# kegmon_hx711.net
KiCad netlist of a schematic drawn in EAGLE
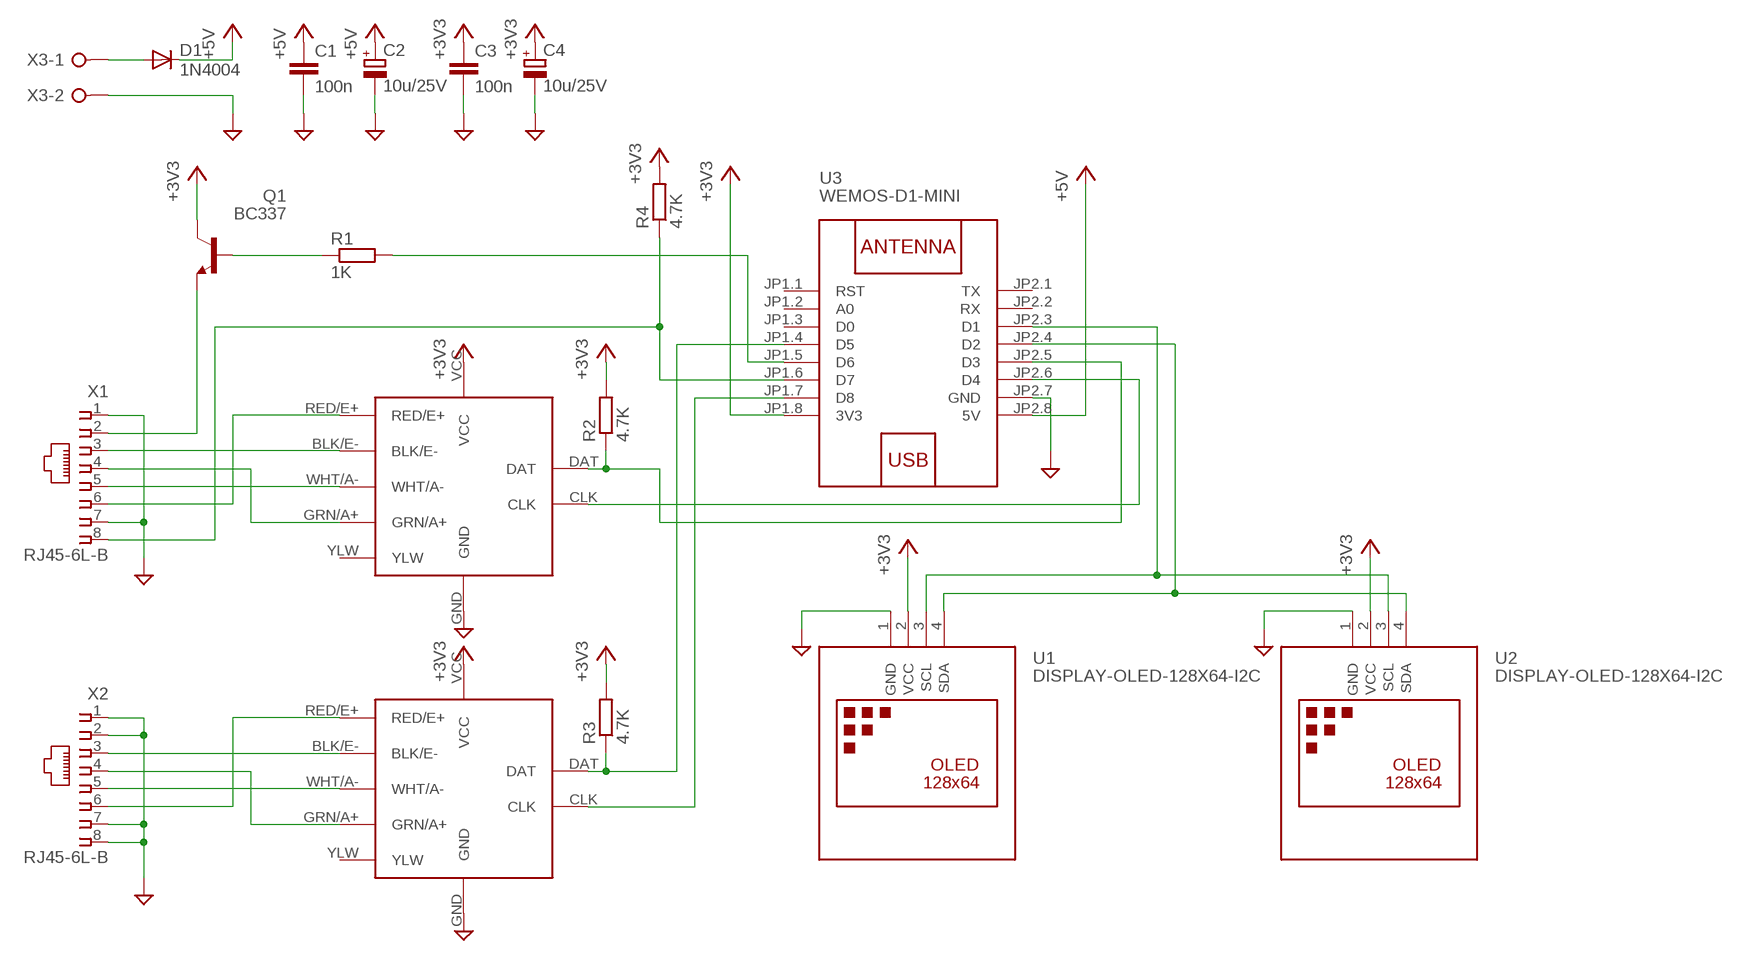
[diagram p0: schematic, sheet 1]

(export (version "E")
  (design (tool "Eeschema 10.0.6"))
  (components
    (comp (ref "C1")
      (value "100n")
      (footprint "eagle-import:C050-025X075")
      (libsource (lib "eagle-import") (part "C-EU050-025X075"))
    )
    (comp (ref "C2")
      (value "10u/25V")
      (footprint "eagle-import:E2,5-5")
      (libsource (lib "eagle-import") (part "CPOL-EUE2.5-5"))
    )
    (comp (ref "C3")
      (value "100n")
      (footprint "eagle-import:C050-025X075")
      (libsource (lib "eagle-import") (part "C-EU050-025X075"))
    )
    (comp (ref "C4")
      (value "10u/25V")
      (footprint "eagle-import:E2,5-5")
      (libsource (lib "eagle-import") (part "CPOL-EUE2.5-5"))
    )
    (comp (ref "D1")
      (value "1N4004")
      (footprint "eagle-import:DO41-10")
      (libsource (lib "eagle-import") (part "1N4004"))
    )
    (comp (ref "IC1")
      (value "SPARKFUN-HX711")
      (footprint "eagle-import:SPARKFUN-HX711")
      (libsource (lib "eagle-import") (part "SPARKFUN-HX711"))
    )
    (comp (ref "IC2")
      (value "SPARKFUN-HX711")
      (footprint "eagle-import:SPARKFUN-HX711")
      (libsource (lib "eagle-import") (part "SPARKFUN-HX711"))
    )
    (comp (ref "Q1")
      (value "BC337")
      (footprint "eagle-import:TO92")
      (libsource (lib "eagle-import") (part "BC337"))
    )
    (comp (ref "R1")
      (value "1K")
      (footprint "eagle-import:0207_10")
      (libsource (lib "eagle-import") (part "R-EU_0207/10"))
    )
    (comp (ref "R2")
      (value "4.7K")
      (footprint "eagle-import:0207_10")
      (libsource (lib "eagle-import") (part "R-EU_0207/10"))
    )
    (comp (ref "R3")
      (value "4.7K")
      (footprint "eagle-import:0207_10")
      (libsource (lib "eagle-import") (part "R-EU_0207/10"))
    )
    (comp (ref "R4")
      (value "4.7K")
      (footprint "eagle-import:0207_10")
      (libsource (lib "eagle-import") (part "R-EU_0207/10"))
    )
    (comp (ref "U1")
      (value "DISPLAY-OLED-128X64-I2C")
      (footprint "eagle-import:DISPLAY-OLED-128X64-I2C-NOHOLES")
      (libsource (lib "eagle-import") (part "DISPLAY-OLED-128X64-I2CDISPLAY-OLED-128X64-I2C-NOHOLES"))
    )
    (comp (ref "U2")
      (value "DISPLAY-OLED-128X64-I2C")
      (footprint "eagle-import:DISPLAY-OLED-128X64-I2C-NOHOLES")
      (libsource (lib "eagle-import") (part "DISPLAY-OLED-128X64-I2CDISPLAY-OLED-128X64-I2C-NOHOLES"))
    )
    (comp (ref "U3")
      (value "WEMOS-D1-MINI")
      (footprint "eagle-import:WEMOS-D1-MINI")
      (libsource (lib "eagle-import") (part "WEMOS-D1-MINI"))
    )
    (comp (ref "X1")
      (value "RJ45-6L-B")
      (footprint "eagle-import:RJ45-NO-SHIELD")
      (libsource (lib "eagle-import") (part "RJ45-6L-B"))
    )
    (comp (ref "X2")
      (value "RJ45-6L-B")
      (footprint "eagle-import:RJ45-NO-SHIELD")
      (libsource (lib "eagle-import") (part "RJ45-6L-B"))
    )
    (comp (ref "X3")
      (value "W237-02P")
      (footprint "eagle-import:W237-132")
      (libsource (lib "eagle-import") (part "W237-02P"))
    )
  )
  (nets
    (net (code "1") (name "+3V3") (class "Default")
      (node (ref "C3") (pin "1") (pinfunction "1_1") (pintype "passive"))
      (node (ref "C4") (pin "+") (pinfunction "+_+") (pintype "passive"))
      (node (ref "IC1") (pin "VCC") (pinfunction "VCC_VCC") (pintype "bidirectional"))
      (node (ref "IC2") (pin "VCC") (pinfunction "VCC_VCC") (pintype "bidirectional"))
      (node (ref "Q1") (pin "3") (pinfunction "C_3") (pintype "passive"))
      (node (ref "R2") (pin "2") (pinfunction "2_2") (pintype "passive"))
      (node (ref "R3") (pin "2") (pinfunction "2_2") (pintype "passive"))
      (node (ref "R4") (pin "2") (pinfunction "2_2") (pintype "passive"))
      (node (ref "U1") (pin "2") (pinfunction "VCC_2") (pintype "power_in"))
      (node (ref "U2") (pin "2") (pinfunction "VCC_2") (pintype "power_in"))
      (node (ref "U3") (pin "JP1.8") (pinfunction "3V3_JP1.8") (pintype "power_in"))
    )
    (net (code "2") (name "+5V") (class "Default")
      (node (ref "C1") (pin "1") (pinfunction "1_1") (pintype "passive"))
      (node (ref "C2") (pin "+") (pinfunction "+_+") (pintype "passive"))
      (node (ref "D1") (pin "C") (pinfunction "C_C") (pintype "passive"))
      (node (ref "U3") (pin "JP2.8") (pinfunction "5V_JP2.8") (pintype "power_in"))
    )
    (net (code "3") (name "GND") (class "Default")
      (node (ref "C1") (pin "2") (pinfunction "2_2") (pintype "passive"))
      (node (ref "C2") (pin "-") (pinfunction "-_-") (pintype "passive"))
      (node (ref "C3") (pin "2") (pinfunction "2_2") (pintype "passive"))
      (node (ref "C4") (pin "-") (pinfunction "-_-") (pintype "passive"))
      (node (ref "IC1") (pin "GND") (pinfunction "GND_GND") (pintype "bidirectional"))
      (node (ref "IC2") (pin "GND") (pinfunction "GND_GND") (pintype "bidirectional"))
      (node (ref "U1") (pin "1") (pinfunction "GND_1") (pintype "power_in"))
      (node (ref "U2") (pin "1") (pinfunction "GND_1") (pintype "power_in"))
      (node (ref "U3") (pin "JP2.7") (pinfunction "GND_JP2.7") (pintype "power_in"))
      (node (ref "X1") (pin "1") (pinfunction "1_1") (pintype "passive"))
      (node (ref "X1") (pin "7") (pinfunction "7_7") (pintype "passive"))
      (node (ref "X2") (pin "1") (pinfunction "1_1") (pintype "passive"))
      (node (ref "X2") (pin "2") (pinfunction "2_2") (pintype "passive"))
      (node (ref "X2") (pin "7") (pinfunction "7_7") (pintype "passive"))
      (node (ref "X2") (pin "8") (pinfunction "8_8") (pintype "passive"))
      (node (ref "X3") (pin "2") (pinfunction "KL_2") (pintype "passive"))
    )
    (net (code "4") (name "Net-(IC1-PadBLK{slash}E-)") (class "Default")
      (node (ref "IC1") (pin "BLK/E-") (pinfunction "BLK/E-_BLK/E-") (pintype "bidirectional"))
      (node (ref "X1") (pin "3") (pinfunction "3_3") (pintype "passive"))
    )
    (net (code "5") (name "Net-(IC1-PadGRN{slash}A+)") (class "Default")
      (node (ref "IC1") (pin "GRN/A+") (pinfunction "GRN/A+_GRN/A+") (pintype "bidirectional"))
      (node (ref "X1") (pin "4") (pinfunction "4_4") (pintype "passive"))
    )
    (net (code "6") (name "Net-(IC1-PadRED{slash}E+)") (class "Default")
      (node (ref "IC1") (pin "RED/E+") (pinfunction "RED/E+_RED/E+") (pintype "bidirectional"))
      (node (ref "X1") (pin "6") (pinfunction "6_6") (pintype "passive"))
    )
    (net (code "7") (name "Net-(IC1-PadWHT{slash}A-)") (class "Default")
      (node (ref "IC1") (pin "WHT/A-") (pinfunction "WHT/A-_WHT/A-") (pintype "bidirectional"))
      (node (ref "X1") (pin "5") (pinfunction "5_5") (pintype "passive"))
    )
    (net (code "8") (name "Net-(IC2-PadBLK{slash}E-)") (class "Default")
      (node (ref "IC2") (pin "BLK/E-") (pinfunction "BLK/E-_BLK/E-") (pintype "bidirectional"))
      (node (ref "X2") (pin "3") (pinfunction "3_3") (pintype "passive"))
    )
    (net (code "9") (name "Net-(IC2-PadGRN{slash}A+)") (class "Default")
      (node (ref "IC2") (pin "GRN/A+") (pinfunction "GRN/A+_GRN/A+") (pintype "bidirectional"))
      (node (ref "X2") (pin "4") (pinfunction "4_4") (pintype "passive"))
    )
    (net (code "10") (name "Net-(IC2-PadRED{slash}E+)") (class "Default")
      (node (ref "IC2") (pin "RED/E+") (pinfunction "RED/E+_RED/E+") (pintype "bidirectional"))
      (node (ref "X2") (pin "6") (pinfunction "6_6") (pintype "passive"))
    )
    (net (code "11") (name "Net-(IC2-PadWHT{slash}A-)") (class "Default")
      (node (ref "IC2") (pin "WHT/A-") (pinfunction "WHT/A-_WHT/A-") (pintype "bidirectional"))
      (node (ref "X2") (pin "5") (pinfunction "5_5") (pintype "passive"))
    )
    (net (code "12") (name "Net-(Q1-B)") (class "Default")
      (node (ref "Q1") (pin "2") (pinfunction "B_2") (pintype "passive"))
      (node (ref "R1") (pin "1") (pinfunction "1_1") (pintype "passive"))
    )
    (net (code "13") (name "Net-(Q1-E)") (class "Default")
      (node (ref "Q1") (pin "1") (pinfunction "E_1") (pintype "passive"))
      (node (ref "X1") (pin "2") (pinfunction "2_2") (pintype "passive"))
    )
    (net (code "14") (name "Net-(U1-SCL)") (class "Default")
      (node (ref "U1") (pin "3") (pinfunction "SCL_3") (pintype "bidirectional"))
      (node (ref "U2") (pin "3") (pinfunction "SCL_3") (pintype "bidirectional"))
      (node (ref "U3") (pin "JP2.3") (pinfunction "D1_JP2.3") (pintype "bidirectional"))
    )
    (net (code "15") (name "Net-(U1-SDA)") (class "Default")
      (node (ref "U1") (pin "4") (pinfunction "SDA_4") (pintype "bidirectional"))
      (node (ref "U2") (pin "4") (pinfunction "SDA_4") (pintype "bidirectional"))
      (node (ref "U3") (pin "JP2.4") (pinfunction "D2_JP2.4") (pintype "bidirectional"))
    )
    (net (code "16") (name "Net-(U3-D3)") (class "Default")
      (node (ref "IC1") (pin "DAT") (pinfunction "DAT_DAT") (pintype "bidirectional"))
      (node (ref "R2") (pin "1") (pinfunction "1_1") (pintype "passive"))
      (node (ref "U3") (pin "JP2.5") (pinfunction "D3_JP2.5") (pintype "bidirectional"))
    )
    (net (code "17") (name "Net-(U3-D4)") (class "Default")
      (node (ref "IC1") (pin "CLK") (pinfunction "CLK_CLK") (pintype "bidirectional"))
      (node (ref "U3") (pin "JP2.6") (pinfunction "D4_JP2.6") (pintype "bidirectional"))
    )
    (net (code "18") (name "Net-(U3-D5)") (class "Default")
      (node (ref "IC2") (pin "DAT") (pinfunction "DAT_DAT") (pintype "bidirectional"))
      (node (ref "R3") (pin "1") (pinfunction "1_1") (pintype "passive"))
      (node (ref "U3") (pin "JP1.4") (pinfunction "D5_JP1.4") (pintype "bidirectional"))
    )
    (net (code "19") (name "Net-(U3-D6)") (class "Default")
      (node (ref "R1") (pin "2") (pinfunction "2_2") (pintype "passive"))
      (node (ref "U3") (pin "JP1.5") (pinfunction "D6_JP1.5") (pintype "bidirectional"))
    )
    (net (code "20") (name "Net-(U3-D7)") (class "Default")
      (node (ref "R4") (pin "1") (pinfunction "1_1") (pintype "passive"))
      (node (ref "U3") (pin "JP1.6") (pinfunction "D7_JP1.6") (pintype "bidirectional"))
      (node (ref "X1") (pin "8") (pinfunction "8_8") (pintype "passive"))
    )
    (net (code "21") (name "Net-(U3-D8)") (class "Default")
      (node (ref "IC2") (pin "CLK") (pinfunction "CLK_CLK") (pintype "bidirectional"))
      (node (ref "U3") (pin "JP1.7") (pinfunction "D8_JP1.7") (pintype "bidirectional"))
    )
    (net (code "22") (name "Net-(X3A-KL)") (class "Default")
      (node (ref "D1") (pin "A") (pinfunction "A_A") (pintype "passive"))
      (node (ref "X3") (pin "1") (pinfunction "KL_1") (pintype "passive"))
    )
    (net (code "23") (name "unconnected-(IC1-PadYLW)") (class "Default")
      (node (ref "IC1") (pin "YLW") (pinfunction "YLW_YLW") (pintype "bidirectional"))
    )
    (net (code "24") (name "unconnected-(IC2-PadYLW)") (class "Default")
      (node (ref "IC2") (pin "YLW") (pinfunction "YLW_YLW") (pintype "bidirectional"))
    )
    (net (code "25") (name "unconnected-(U3-A0-PadJP1.2)") (class "Default")
      (node (ref "U3") (pin "JP1.2") (pinfunction "A0_JP1.2") (pintype "bidirectional"))
    )
    (net (code "26") (name "unconnected-(U3-D0-PadJP1.3)") (class "Default")
      (node (ref "U3") (pin "JP1.3") (pinfunction "D0_JP1.3") (pintype "bidirectional"))
    )
    (net (code "27") (name "unconnected-(U3-RST-PadJP1.1)") (class "Default")
      (node (ref "U3") (pin "JP1.1") (pinfunction "RST_JP1.1") (pintype "bidirectional"))
    )
    (net (code "28") (name "unconnected-(U3-RX-PadJP2.2)") (class "Default")
      (node (ref "U3") (pin "JP2.2") (pinfunction "RX_JP2.2") (pintype "bidirectional"))
    )
    (net (code "29") (name "unconnected-(U3-TX-PadJP2.1)") (class "Default")
      (node (ref "U3") (pin "JP2.1") (pinfunction "TX_JP2.1") (pintype "bidirectional"))
    )
  )
)
